# DBL_TLC5940_driver_for_High_load.net
KiCad netlist of a schematic drawn in Altium Designer
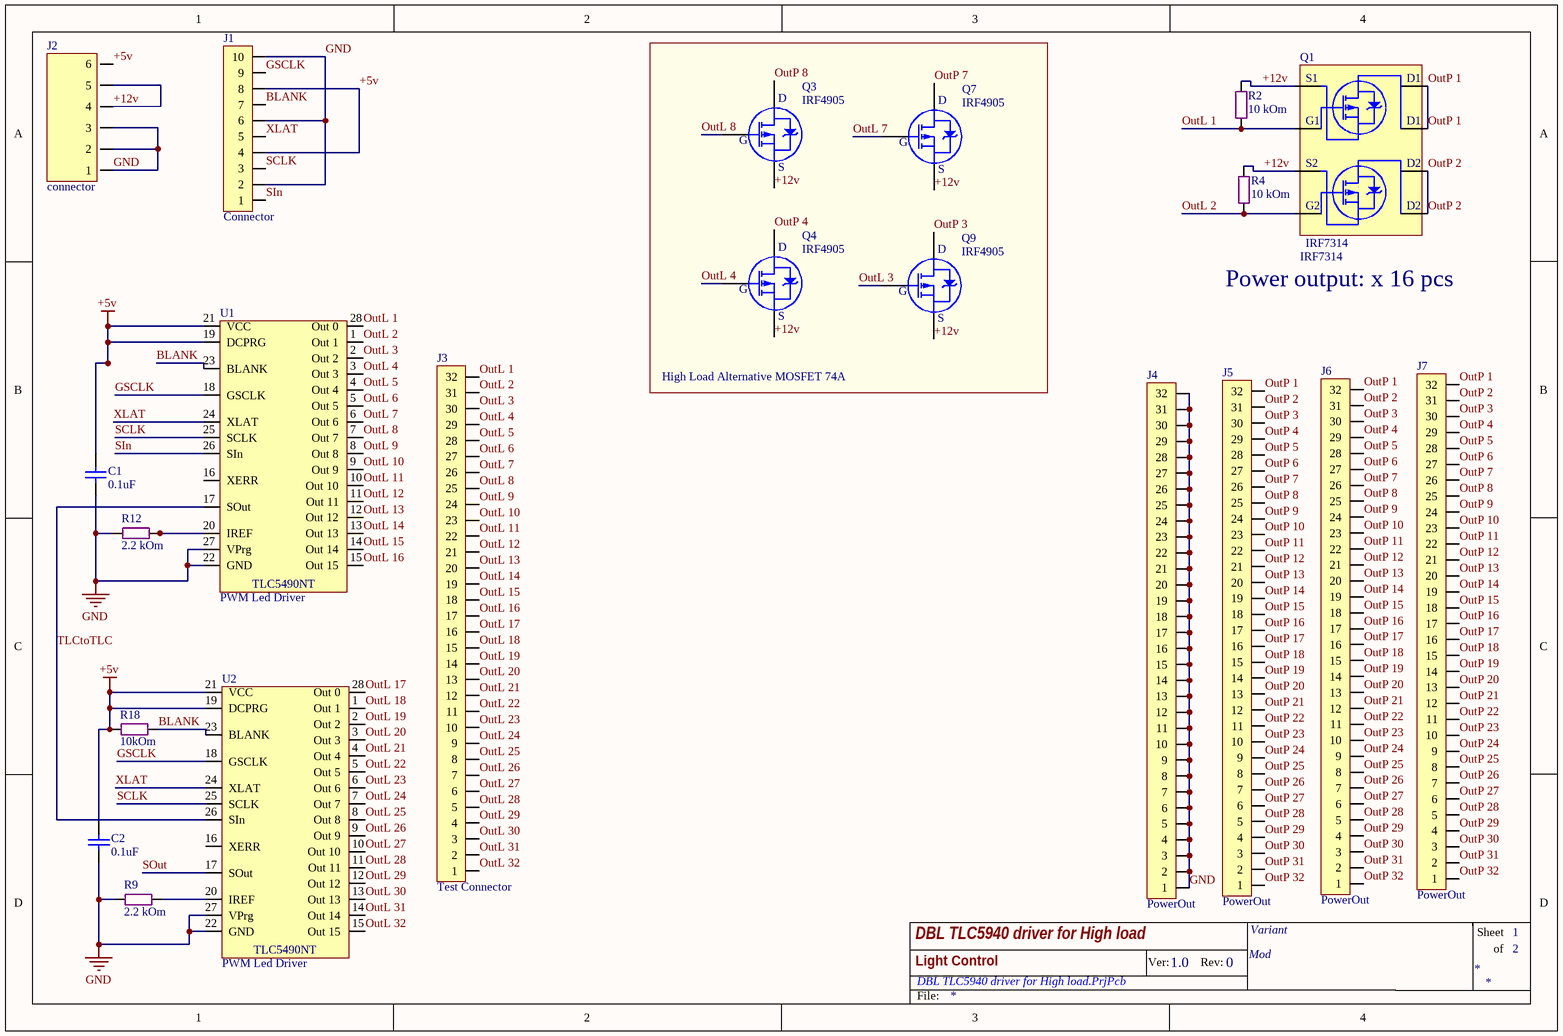
[diagram p0: DBL TLC5940 driver for High load.SchDoc]

(export (version "E")
  (design (tool "Eeschema 10.0.6"))
  (components
    (comp (ref "C1")
      (value "0.1uF")
      (footprint "Capacitor:SMD 0805 (2012)")
      (description "Capacitor")
      (libsource (lib "Capacitor") (part "Cap SMD 0402-1812"))
    )
    (comp (ref "C2")
      (value "0.1uF")
      (footprint "Capacitor:SMD 0805 (2012)")
      (description "Capacitor")
      (libsource (lib "Capacitor") (part "Cap SMD 0402-1812"))
    )
    (comp (ref "J1")
      (value "Connector")
      (footprint "Connector:LINE 2.54 x 10D (2 x 5) - BH")
      (description "Vert, Dbl line, Male")
      (libsource (lib "Connector") (part "PLD-10 (2 x 5)"))
    )
    (comp (ref "J2")
      (value "connector")
      (footprint "Connector:Molex Mini-Fit Jr - 6Pin R")
      (description "Right, Dbl line, Female")
      (libsource (lib "Connector") (part "Molex Mini-Fit Jr - 6 pin"))
    )
    (comp (ref "J3")
      (value "Test Connector")
      (footprint "Connector:LINE 2.54 x 32")
      (description "Vert, Sgl line, Male")
      (libsource (lib "Connector") (part "PLS-32"))
    )
    (comp (ref "J4")
      (value "PowerOut")
      (footprint "Connector:LINE 2.54 x 32")
      (description "Vert, Sgl line, Male")
      (libsource (lib "Connector") (part "PLS-32"))
    )
    (comp (ref "J5")
      (value "PowerOut")
      (footprint "Connector:LINE 2.54 x 32")
      (description "Vert, Sgl line, Male")
      (libsource (lib "Connector") (part "PLS-32"))
    )
    (comp (ref "J6")
      (value "PowerOut")
      (footprint "Connector:LINE 2.54 x 32")
      (description "Vert, Sgl line, Male")
      (libsource (lib "Connector") (part "PLS-32"))
    )
    (comp (ref "J7")
      (value "PowerOut")
      (footprint "Connector:LINE 2.54 x 32")
      (description "Vert, Sgl line, Male")
      (libsource (lib "Connector") (part "PLS-32"))
    )
    (comp (ref "Q1")
      (value "IRF7314")
      (footprint "GeneralCases:SO8")
      (description "Dual P-Ch  20V - 0.058Ω - 5.3A")
      (libsource (lib "Transistor") (part "IRF7314"))
    )
    (comp (ref "Q3")
      (value "IRF4905")
      (footprint "GeneralCases:TO220-2")
      (description "P-Channel 55V - 0.02Ω - 74A")
      (libsource (lib "Transistor") (part "IRF4905"))
    )
    (comp (ref "Q4")
      (value "IRF4905")
      (footprint "GeneralCases:TO220-2")
      (description "P-Channel 55V - 0.02Ω - 74A")
      (libsource (lib "Transistor") (part "IRF4905"))
    )
    (comp (ref "Q7")
      (value "IRF4905")
      (footprint "GeneralCases:TO220-2")
      (description "P-Channel 55V - 0.02Ω - 74A")
      (libsource (lib "Transistor") (part "IRF4905"))
    )
    (comp (ref "Q9")
      (value "IRF4905")
      (footprint "GeneralCases:TO220-2")
      (description "P-Channel 55V - 0.02Ω - 74A")
      (libsource (lib "Transistor") (part "IRF4905"))
    )
    (comp (ref "R2")
      (value "10 kOm")
      (footprint "PassiveComponents:SMD 0805 (2012)")
      (libsource (lib "PassiveComponents") (part "Res All Types"))
    )
    (comp (ref "R4")
      (value "10 kOm")
      (footprint "PassiveComponents:SMD 0805 (2012)")
      (libsource (lib "PassiveComponents") (part "Res All Types"))
    )
    (comp (ref "R9")
      (value "2.2 kOm")
      (footprint "PassiveComponents:SMD 0805 (2012)")
      (libsource (lib "PassiveComponents") (part "Res All Types"))
    )
    (comp (ref "R12")
      (value "2.2 kOm")
      (footprint "PassiveComponents:SMD 0805 (2012)")
      (libsource (lib "PassiveComponents") (part "Res All Types"))
    )
    (comp (ref "R18")
      (value "10kOm")
      (footprint "PassiveComponents:SMD 0805 (2012)")
      (libsource (lib "PassiveComponents") (part "Res All Types"))
    )
    (comp (ref "U1")
      (value "PWM Led Driver")
      (footprint "GeneralCases:DIP-28 (OVAL)")
      (description "16-Channel LED Driver With DOT Correction and Grayscale PWM Control")
      (libsource (lib "Chips") (part "TLC5940"))
    )
    (comp (ref "U2")
      (value "PWM Led Driver")
      (footprint "GeneralCases:DIP-28 (OVAL)")
      (description "16-Channel LED Driver With DOT Correction and Grayscale PWM Control")
      (libsource (lib "Chips") (part "TLC5940"))
    )
  )
  (nets
    (net (code "1") (name "+5v") (class "Default")
      (node (ref "C1") (pin "1") (pinfunction "1_1") (pintype "passive"))
      (node (ref "C2") (pin "1") (pinfunction "1_1") (pintype "passive"))
      (node (ref "J1") (pin "4") (pinfunction "4_4") (pintype "passive"))
      (node (ref "J1") (pin "8") (pinfunction "8_8") (pintype "passive"))
      (node (ref "J2") (pin "6") (pinfunction "6_6") (pintype "passive"))
      (node (ref "R18") (pin "1") (pinfunction "1_1") (pintype "passive"))
      (node (ref "U1") (pin "19") (pinfunction "DCPRG_19") (pintype "passive"))
      (node (ref "U1") (pin "21") (pinfunction "VCC_21") (pintype "passive"))
      (node (ref "U2") (pin "19") (pinfunction "DCPRG_19") (pintype "passive"))
      (node (ref "U2") (pin "21") (pinfunction "VCC_21") (pintype "passive"))
    )
    (net (code "2") (name "/+12v") (class "Default")
      (node (ref "J2") (pin "4") (pinfunction "4_4") (pintype "passive"))
      (node (ref "J2") (pin "5") (pinfunction "5_5") (pintype "passive"))
      (node (ref "Q1") (pin "1") (pinfunction "S_1") (pintype "passive"))
      (node (ref "Q1") (pin "3") (pinfunction "S_3") (pintype "passive"))
      (node (ref "Q3") (pin "3") (pinfunction "S_3") (pintype "passive"))
      (node (ref "Q4") (pin "3") (pinfunction "S_3") (pintype "passive"))
      (node (ref "Q7") (pin "3") (pinfunction "S_3") (pintype "passive"))
      (node (ref "Q9") (pin "3") (pinfunction "S_3") (pintype "passive"))
      (node (ref "R2") (pin "2") (pinfunction "2_2") (pintype "passive"))
      (node (ref "R4") (pin "2") (pinfunction "2_2") (pintype "passive"))
    )
    (net (code "3") (name "/BLANK") (class "Default")
      (node (ref "J1") (pin "7") (pinfunction "7_7") (pintype "passive"))
      (node (ref "R18") (pin "2") (pinfunction "2_2") (pintype "passive"))
      (node (ref "U1") (pin "23") (pinfunction "BLANK_23") (pintype "passive"))
      (node (ref "U2") (pin "23") (pinfunction "BLANK_23") (pintype "passive"))
    )
    (net (code "4") (name "/GSCLK") (class "Default")
      (node (ref "J1") (pin "9") (pinfunction "9_9") (pintype "passive"))
      (node (ref "U1") (pin "18") (pinfunction "GSCLK_18") (pintype "passive"))
      (node (ref "U2") (pin "18") (pinfunction "GSCLK_18") (pintype "passive"))
    )
    (net (code "5") (name "/OutL 1") (class "Default")
      (node (ref "J3") (pin "32") (pinfunction "32_32") (pintype "passive"))
      (node (ref "Q1") (pin "2") (pinfunction "G_2") (pintype "passive"))
      (node (ref "R2") (pin "1") (pinfunction "1_1") (pintype "passive"))
      (node (ref "U1") (pin "28") (pinfunction "Out_0_28") (pintype "passive"))
    )
    (net (code "6") (name "/OutL 2") (class "Default")
      (node (ref "J3") (pin "31") (pinfunction "31_31") (pintype "passive"))
      (node (ref "Q1") (pin "4") (pinfunction "G_4") (pintype "passive"))
      (node (ref "R4") (pin "1") (pinfunction "1_1") (pintype "passive"))
      (node (ref "U1") (pin "1") (pinfunction "Out_1_1") (pintype "passive"))
    )
    (net (code "7") (name "/OutL 3") (class "Default")
      (node (ref "J3") (pin "30") (pinfunction "30_30") (pintype "passive"))
      (node (ref "Q9") (pin "1") (pinfunction "G_1") (pintype "passive"))
      (node (ref "U1") (pin "2") (pinfunction "Out_2_2") (pintype "passive"))
    )
    (net (code "8") (name "/OutL 4") (class "Default")
      (node (ref "J3") (pin "29") (pinfunction "29_29") (pintype "passive"))
      (node (ref "Q4") (pin "1") (pinfunction "G_1") (pintype "passive"))
      (node (ref "U1") (pin "3") (pinfunction "Out_3_3") (pintype "passive"))
    )
    (net (code "9") (name "/OutL 5") (class "Default")
      (node (ref "J3") (pin "28") (pinfunction "28_28") (pintype "passive"))
      (node (ref "U1") (pin "4") (pinfunction "Out_4_4") (pintype "passive"))
    )
    (net (code "10") (name "/OutL 6") (class "Default")
      (node (ref "J3") (pin "27") (pinfunction "27_27") (pintype "passive"))
      (node (ref "U1") (pin "5") (pinfunction "Out_5_5") (pintype "passive"))
    )
    (net (code "11") (name "/OutL 7") (class "Default")
      (node (ref "J3") (pin "26") (pinfunction "26_26") (pintype "passive"))
      (node (ref "Q7") (pin "1") (pinfunction "G_1") (pintype "passive"))
      (node (ref "U1") (pin "6") (pinfunction "Out_6_6") (pintype "passive"))
    )
    (net (code "12") (name "/OutL 8") (class "Default")
      (node (ref "J3") (pin "25") (pinfunction "25_25") (pintype "passive"))
      (node (ref "Q3") (pin "1") (pinfunction "G_1") (pintype "passive"))
      (node (ref "U1") (pin "7") (pinfunction "Out_7_7") (pintype "passive"))
    )
    (net (code "13") (name "/OutL 9") (class "Default")
      (node (ref "J3") (pin "24") (pinfunction "24_24") (pintype "passive"))
      (node (ref "U1") (pin "8") (pinfunction "Out_8_8") (pintype "passive"))
    )
    (net (code "14") (name "/OutL 10") (class "Default")
      (node (ref "J3") (pin "23") (pinfunction "23_23") (pintype "passive"))
      (node (ref "U1") (pin "9") (pinfunction "Out_9_9") (pintype "passive"))
    )
    (net (code "15") (name "/OutL 11") (class "Default")
      (node (ref "J3") (pin "22") (pinfunction "22_22") (pintype "passive"))
      (node (ref "U1") (pin "10") (pinfunction "Out_10_10") (pintype "passive"))
    )
    (net (code "16") (name "/OutL 12") (class "Default")
      (node (ref "J3") (pin "21") (pinfunction "21_21") (pintype "passive"))
      (node (ref "U1") (pin "11") (pinfunction "Out_11_11") (pintype "passive"))
    )
    (net (code "17") (name "/OutL 13") (class "Default")
      (node (ref "J3") (pin "20") (pinfunction "20_20") (pintype "passive"))
      (node (ref "U1") (pin "12") (pinfunction "Out_12_12") (pintype "passive"))
    )
    (net (code "18") (name "/OutL 14") (class "Default")
      (node (ref "J3") (pin "19") (pinfunction "19_19") (pintype "passive"))
      (node (ref "U1") (pin "13") (pinfunction "Out_13_13") (pintype "passive"))
    )
    (net (code "19") (name "/OutL 15") (class "Default")
      (node (ref "J3") (pin "18") (pinfunction "18_18") (pintype "passive"))
      (node (ref "U1") (pin "14") (pinfunction "Out_14_14") (pintype "passive"))
    )
    (net (code "20") (name "/OutL 16") (class "Default")
      (node (ref "J3") (pin "17") (pinfunction "17_17") (pintype "passive"))
      (node (ref "U1") (pin "15") (pinfunction "Out_15_15") (pintype "passive"))
    )
    (net (code "21") (name "/OutL 17") (class "Default")
      (node (ref "J3") (pin "16") (pinfunction "16_16") (pintype "passive"))
      (node (ref "U2") (pin "28") (pinfunction "Out_0_28") (pintype "passive"))
    )
    (net (code "22") (name "/OutL 18") (class "Default")
      (node (ref "J3") (pin "15") (pinfunction "15_15") (pintype "passive"))
      (node (ref "U2") (pin "1") (pinfunction "Out_1_1") (pintype "passive"))
    )
    (net (code "23") (name "/OutL 19") (class "Default")
      (node (ref "J3") (pin "14") (pinfunction "14_14") (pintype "passive"))
      (node (ref "U2") (pin "2") (pinfunction "Out_2_2") (pintype "passive"))
    )
    (net (code "24") (name "/OutL 20") (class "Default")
      (node (ref "J3") (pin "13") (pinfunction "13_13") (pintype "passive"))
      (node (ref "U2") (pin "3") (pinfunction "Out_3_3") (pintype "passive"))
    )
    (net (code "25") (name "/OutL 21") (class "Default")
      (node (ref "J3") (pin "12") (pinfunction "12_12") (pintype "passive"))
      (node (ref "U2") (pin "4") (pinfunction "Out_4_4") (pintype "passive"))
    )
    (net (code "26") (name "/OutL 22") (class "Default")
      (node (ref "J3") (pin "11") (pinfunction "11_11") (pintype "passive"))
      (node (ref "U2") (pin "5") (pinfunction "Out_5_5") (pintype "passive"))
    )
    (net (code "27") (name "/OutL 23") (class "Default")
      (node (ref "J3") (pin "10") (pinfunction "10_10") (pintype "passive"))
      (node (ref "U2") (pin "6") (pinfunction "Out_6_6") (pintype "passive"))
    )
    (net (code "28") (name "/OutL 24") (class "Default")
      (node (ref "J3") (pin "9") (pinfunction "9_9") (pintype "passive"))
      (node (ref "U2") (pin "7") (pinfunction "Out_7_7") (pintype "passive"))
    )
    (net (code "29") (name "/OutL 25") (class "Default")
      (node (ref "J3") (pin "8") (pinfunction "8_8") (pintype "passive"))
      (node (ref "U2") (pin "8") (pinfunction "Out_8_8") (pintype "passive"))
    )
    (net (code "30") (name "/OutL 26") (class "Default")
      (node (ref "J3") (pin "7") (pinfunction "7_7") (pintype "passive"))
      (node (ref "U2") (pin "9") (pinfunction "Out_9_9") (pintype "passive"))
    )
    (net (code "31") (name "/OutL 27") (class "Default")
      (node (ref "J3") (pin "6") (pinfunction "6_6") (pintype "passive"))
      (node (ref "U2") (pin "10") (pinfunction "Out_10_10") (pintype "passive"))
    )
    (net (code "32") (name "/OutL 28") (class "Default")
      (node (ref "J3") (pin "5") (pinfunction "5_5") (pintype "passive"))
      (node (ref "U2") (pin "11") (pinfunction "Out_11_11") (pintype "passive"))
    )
    (net (code "33") (name "/OutL 29") (class "Default")
      (node (ref "J3") (pin "4") (pinfunction "4_4") (pintype "passive"))
      (node (ref "U2") (pin "12") (pinfunction "Out_12_12") (pintype "passive"))
    )
    (net (code "34") (name "/OutL 30") (class "Default")
      (node (ref "J3") (pin "3") (pinfunction "3_3") (pintype "passive"))
      (node (ref "U2") (pin "13") (pinfunction "Out_13_13") (pintype "passive"))
    )
    (net (code "35") (name "/OutL 31") (class "Default")
      (node (ref "J3") (pin "2") (pinfunction "2_2") (pintype "passive"))
      (node (ref "U2") (pin "14") (pinfunction "Out_14_14") (pintype "passive"))
    )
    (net (code "36") (name "/OutL 32") (class "Default")
      (node (ref "J3") (pin "1") (pinfunction "1_1") (pintype "passive"))
      (node (ref "U2") (pin "15") (pinfunction "Out_15_15") (pintype "passive"))
    )
    (net (code "37") (name "/OutP 1") (class "Default")
      (node (ref "J5") (pin "32") (pinfunction "32_32") (pintype "passive"))
      (node (ref "J6") (pin "32") (pinfunction "32_32") (pintype "passive"))
      (node (ref "J7") (pin "32") (pinfunction "32_32") (pintype "passive"))
      (node (ref "Q1") (pin "7") (pinfunction "D_7") (pintype "passive"))
      (node (ref "Q1") (pin "8") (pinfunction "D_8") (pintype "passive"))
    )
    (net (code "38") (name "/OutP 2") (class "Default")
      (node (ref "J5") (pin "31") (pinfunction "31_31") (pintype "passive"))
      (node (ref "J6") (pin "31") (pinfunction "31_31") (pintype "passive"))
      (node (ref "J7") (pin "31") (pinfunction "31_31") (pintype "passive"))
      (node (ref "Q1") (pin "5") (pinfunction "D_5") (pintype "passive"))
      (node (ref "Q1") (pin "6") (pinfunction "D_6") (pintype "passive"))
    )
    (net (code "39") (name "/OutP 3") (class "Default")
      (node (ref "J5") (pin "30") (pinfunction "30_30") (pintype "passive"))
      (node (ref "J6") (pin "30") (pinfunction "30_30") (pintype "passive"))
      (node (ref "J7") (pin "30") (pinfunction "30_30") (pintype "passive"))
      (node (ref "Q9") (pin "2") (pinfunction "D_2") (pintype "passive"))
    )
    (net (code "40") (name "/OutP 4") (class "Default")
      (node (ref "J5") (pin "29") (pinfunction "29_29") (pintype "passive"))
      (node (ref "J6") (pin "29") (pinfunction "29_29") (pintype "passive"))
      (node (ref "J7") (pin "29") (pinfunction "29_29") (pintype "passive"))
      (node (ref "Q4") (pin "2") (pinfunction "D_2") (pintype "passive"))
    )
    (net (code "41") (name "/OutP 5") (class "Default")
      (node (ref "J5") (pin "28") (pinfunction "28_28") (pintype "passive"))
      (node (ref "J6") (pin "28") (pinfunction "28_28") (pintype "passive"))
      (node (ref "J7") (pin "28") (pinfunction "28_28") (pintype "passive"))
    )
    (net (code "42") (name "/OutP 6") (class "Default")
      (node (ref "J5") (pin "27") (pinfunction "27_27") (pintype "passive"))
      (node (ref "J6") (pin "27") (pinfunction "27_27") (pintype "passive"))
      (node (ref "J7") (pin "27") (pinfunction "27_27") (pintype "passive"))
    )
    (net (code "43") (name "/OutP 7") (class "Default")
      (node (ref "J5") (pin "26") (pinfunction "26_26") (pintype "passive"))
      (node (ref "J6") (pin "26") (pinfunction "26_26") (pintype "passive"))
      (node (ref "J7") (pin "26") (pinfunction "26_26") (pintype "passive"))
      (node (ref "Q7") (pin "2") (pinfunction "D_2") (pintype "passive"))
    )
    (net (code "44") (name "/OutP 8") (class "Default")
      (node (ref "J5") (pin "25") (pinfunction "25_25") (pintype "passive"))
      (node (ref "J6") (pin "25") (pinfunction "25_25") (pintype "passive"))
      (node (ref "J7") (pin "25") (pinfunction "25_25") (pintype "passive"))
      (node (ref "Q3") (pin "2") (pinfunction "D_2") (pintype "passive"))
    )
    (net (code "45") (name "/OutP 9") (class "Default")
      (node (ref "J5") (pin "24") (pinfunction "24_24") (pintype "passive"))
      (node (ref "J6") (pin "24") (pinfunction "24_24") (pintype "passive"))
      (node (ref "J7") (pin "24") (pinfunction "24_24") (pintype "passive"))
    )
    (net (code "46") (name "/OutP 10") (class "Default")
      (node (ref "J5") (pin "23") (pinfunction "23_23") (pintype "passive"))
      (node (ref "J6") (pin "23") (pinfunction "23_23") (pintype "passive"))
      (node (ref "J7") (pin "23") (pinfunction "23_23") (pintype "passive"))
    )
    (net (code "47") (name "/OutP 11") (class "Default")
      (node (ref "J5") (pin "22") (pinfunction "22_22") (pintype "passive"))
      (node (ref "J6") (pin "22") (pinfunction "22_22") (pintype "passive"))
      (node (ref "J7") (pin "22") (pinfunction "22_22") (pintype "passive"))
    )
    (net (code "48") (name "/OutP 12") (class "Default")
      (node (ref "J5") (pin "21") (pinfunction "21_21") (pintype "passive"))
      (node (ref "J6") (pin "21") (pinfunction "21_21") (pintype "passive"))
      (node (ref "J7") (pin "21") (pinfunction "21_21") (pintype "passive"))
    )
    (net (code "49") (name "/OutP 13") (class "Default")
      (node (ref "J5") (pin "20") (pinfunction "20_20") (pintype "passive"))
      (node (ref "J6") (pin "20") (pinfunction "20_20") (pintype "passive"))
      (node (ref "J7") (pin "20") (pinfunction "20_20") (pintype "passive"))
    )
    (net (code "50") (name "/OutP 14") (class "Default")
      (node (ref "J5") (pin "19") (pinfunction "19_19") (pintype "passive"))
      (node (ref "J6") (pin "19") (pinfunction "19_19") (pintype "passive"))
      (node (ref "J7") (pin "19") (pinfunction "19_19") (pintype "passive"))
    )
    (net (code "51") (name "/OutP 15") (class "Default")
      (node (ref "J5") (pin "18") (pinfunction "18_18") (pintype "passive"))
      (node (ref "J6") (pin "18") (pinfunction "18_18") (pintype "passive"))
      (node (ref "J7") (pin "18") (pinfunction "18_18") (pintype "passive"))
    )
    (net (code "52") (name "/OutP 16") (class "Default")
      (node (ref "J5") (pin "17") (pinfunction "17_17") (pintype "passive"))
      (node (ref "J6") (pin "17") (pinfunction "17_17") (pintype "passive"))
      (node (ref "J7") (pin "17") (pinfunction "17_17") (pintype "passive"))
    )
    (net (code "53") (name "/OutP 17") (class "Default")
      (node (ref "J5") (pin "16") (pinfunction "16_16") (pintype "passive"))
      (node (ref "J6") (pin "16") (pinfunction "16_16") (pintype "passive"))
      (node (ref "J7") (pin "16") (pinfunction "16_16") (pintype "passive"))
    )
    (net (code "54") (name "/OutP 18") (class "Default")
      (node (ref "J5") (pin "15") (pinfunction "15_15") (pintype "passive"))
      (node (ref "J6") (pin "15") (pinfunction "15_15") (pintype "passive"))
      (node (ref "J7") (pin "15") (pinfunction "15_15") (pintype "passive"))
    )
    (net (code "55") (name "/OutP 19") (class "Default")
      (node (ref "J5") (pin "14") (pinfunction "14_14") (pintype "passive"))
      (node (ref "J6") (pin "14") (pinfunction "14_14") (pintype "passive"))
      (node (ref "J7") (pin "14") (pinfunction "14_14") (pintype "passive"))
    )
    (net (code "56") (name "/OutP 20") (class "Default")
      (node (ref "J5") (pin "13") (pinfunction "13_13") (pintype "passive"))
      (node (ref "J6") (pin "13") (pinfunction "13_13") (pintype "passive"))
      (node (ref "J7") (pin "13") (pinfunction "13_13") (pintype "passive"))
    )
    (net (code "57") (name "/OutP 21") (class "Default")
      (node (ref "J5") (pin "12") (pinfunction "12_12") (pintype "passive"))
      (node (ref "J6") (pin "12") (pinfunction "12_12") (pintype "passive"))
      (node (ref "J7") (pin "12") (pinfunction "12_12") (pintype "passive"))
    )
    (net (code "58") (name "/OutP 22") (class "Default")
      (node (ref "J5") (pin "11") (pinfunction "11_11") (pintype "passive"))
      (node (ref "J6") (pin "11") (pinfunction "11_11") (pintype "passive"))
      (node (ref "J7") (pin "11") (pinfunction "11_11") (pintype "passive"))
    )
    (net (code "59") (name "/OutP 23") (class "Default")
      (node (ref "J5") (pin "10") (pinfunction "10_10") (pintype "passive"))
      (node (ref "J6") (pin "10") (pinfunction "10_10") (pintype "passive"))
      (node (ref "J7") (pin "10") (pinfunction "10_10") (pintype "passive"))
    )
    (net (code "60") (name "/OutP 24") (class "Default")
      (node (ref "J5") (pin "9") (pinfunction "9_9") (pintype "passive"))
      (node (ref "J6") (pin "9") (pinfunction "9_9") (pintype "passive"))
      (node (ref "J7") (pin "9") (pinfunction "9_9") (pintype "passive"))
    )
    (net (code "61") (name "/OutP 25") (class "Default")
      (node (ref "J5") (pin "8") (pinfunction "8_8") (pintype "passive"))
      (node (ref "J6") (pin "8") (pinfunction "8_8") (pintype "passive"))
      (node (ref "J7") (pin "8") (pinfunction "8_8") (pintype "passive"))
    )
    (net (code "62") (name "/OutP 26") (class "Default")
      (node (ref "J5") (pin "7") (pinfunction "7_7") (pintype "passive"))
      (node (ref "J6") (pin "7") (pinfunction "7_7") (pintype "passive"))
      (node (ref "J7") (pin "7") (pinfunction "7_7") (pintype "passive"))
    )
    (net (code "63") (name "/OutP 27") (class "Default")
      (node (ref "J5") (pin "6") (pinfunction "6_6") (pintype "passive"))
      (node (ref "J6") (pin "6") (pinfunction "6_6") (pintype "passive"))
      (node (ref "J7") (pin "6") (pinfunction "6_6") (pintype "passive"))
    )
    (net (code "64") (name "/OutP 28") (class "Default")
      (node (ref "J5") (pin "5") (pinfunction "5_5") (pintype "passive"))
      (node (ref "J6") (pin "5") (pinfunction "5_5") (pintype "passive"))
      (node (ref "J7") (pin "5") (pinfunction "5_5") (pintype "passive"))
    )
    (net (code "65") (name "/OutP 29") (class "Default")
      (node (ref "J5") (pin "4") (pinfunction "4_4") (pintype "passive"))
      (node (ref "J6") (pin "4") (pinfunction "4_4") (pintype "passive"))
      (node (ref "J7") (pin "4") (pinfunction "4_4") (pintype "passive"))
    )
    (net (code "66") (name "/OutP 30") (class "Default")
      (node (ref "J5") (pin "3") (pinfunction "3_3") (pintype "passive"))
      (node (ref "J6") (pin "3") (pinfunction "3_3") (pintype "passive"))
      (node (ref "J7") (pin "3") (pinfunction "3_3") (pintype "passive"))
    )
    (net (code "67") (name "/OutP 31") (class "Default")
      (node (ref "J5") (pin "2") (pinfunction "2_2") (pintype "passive"))
      (node (ref "J6") (pin "2") (pinfunction "2_2") (pintype "passive"))
      (node (ref "J7") (pin "2") (pinfunction "2_2") (pintype "passive"))
    )
    (net (code "68") (name "/OutP 32") (class "Default")
      (node (ref "J5") (pin "1") (pinfunction "1_1") (pintype "passive"))
      (node (ref "J6") (pin "1") (pinfunction "1_1") (pintype "passive"))
      (node (ref "J7") (pin "1") (pinfunction "1_1") (pintype "passive"))
    )
    (net (code "69") (name "/SCLK") (class "Default")
      (node (ref "J1") (pin "3") (pinfunction "3_3") (pintype "passive"))
      (node (ref "U1") (pin "25") (pinfunction "SCLK_25") (pintype "passive"))
      (node (ref "U2") (pin "25") (pinfunction "SCLK_25") (pintype "passive"))
    )
    (net (code "70") (name "/SIn") (class "Default")
      (node (ref "J1") (pin "1") (pinfunction "1_1") (pintype "passive"))
      (node (ref "U1") (pin "26") (pinfunction "SIn_26") (pintype "passive"))
    )
    (net (code "71") (name "/SOut") (class "Default")
      (node (ref "U2") (pin "17") (pinfunction "SOut_17") (pintype "passive"))
    )
    (net (code "72") (name "/TLCtoTLC") (class "Default")
      (node (ref "U1") (pin "17") (pinfunction "SOut_17") (pintype "passive"))
      (node (ref "U2") (pin "26") (pinfunction "SIn_26") (pintype "passive"))
    )
    (net (code "73") (name "/XLAT") (class "Default")
      (node (ref "J1") (pin "5") (pinfunction "5_5") (pintype "passive"))
      (node (ref "U1") (pin "24") (pinfunction "XLAT_24") (pintype "passive"))
      (node (ref "U2") (pin "24") (pinfunction "XLAT_24") (pintype "passive"))
    )
    (net (code "74") (name "GND") (class "Default")
      (node (ref "C1") (pin "2") (pinfunction "2_2") (pintype "passive"))
      (node (ref "C2") (pin "2") (pinfunction "2_2") (pintype "passive"))
      (node (ref "J1") (pin "10") (pinfunction "10_10") (pintype "passive"))
      (node (ref "J1") (pin "2") (pinfunction "2_2") (pintype "passive"))
      (node (ref "J1") (pin "6") (pinfunction "6_6") (pintype "passive"))
      (node (ref "J2") (pin "1") (pinfunction "1_1") (pintype "passive"))
      (node (ref "J2") (pin "2") (pinfunction "2_2") (pintype "passive"))
      (node (ref "J2") (pin "3") (pinfunction "3_3") (pintype "passive"))
      (node (ref "J4") (pin "1") (pinfunction "1_1") (pintype "passive"))
      (node (ref "J4") (pin "10") (pinfunction "10_10") (pintype "passive"))
      (node (ref "J4") (pin "11") (pinfunction "11_11") (pintype "passive"))
      (node (ref "J4") (pin "12") (pinfunction "12_12") (pintype "passive"))
      (node (ref "J4") (pin "13") (pinfunction "13_13") (pintype "passive"))
      (node (ref "J4") (pin "14") (pinfunction "14_14") (pintype "passive"))
      (node (ref "J4") (pin "15") (pinfunction "15_15") (pintype "passive"))
      (node (ref "J4") (pin "16") (pinfunction "16_16") (pintype "passive"))
      (node (ref "J4") (pin "17") (pinfunction "17_17") (pintype "passive"))
      (node (ref "J4") (pin "18") (pinfunction "18_18") (pintype "passive"))
      (node (ref "J4") (pin "19") (pinfunction "19_19") (pintype "passive"))
      (node (ref "J4") (pin "2") (pinfunction "2_2") (pintype "passive"))
      (node (ref "J4") (pin "20") (pinfunction "20_20") (pintype "passive"))
      (node (ref "J4") (pin "21") (pinfunction "21_21") (pintype "passive"))
      (node (ref "J4") (pin "22") (pinfunction "22_22") (pintype "passive"))
      (node (ref "J4") (pin "23") (pinfunction "23_23") (pintype "passive"))
      (node (ref "J4") (pin "24") (pinfunction "24_24") (pintype "passive"))
      (node (ref "J4") (pin "25") (pinfunction "25_25") (pintype "passive"))
      (node (ref "J4") (pin "26") (pinfunction "26_26") (pintype "passive"))
      (node (ref "J4") (pin "27") (pinfunction "27_27") (pintype "passive"))
      (node (ref "J4") (pin "28") (pinfunction "28_28") (pintype "passive"))
      (node (ref "J4") (pin "29") (pinfunction "29_29") (pintype "passive"))
      (node (ref "J4") (pin "3") (pinfunction "3_3") (pintype "passive"))
      (node (ref "J4") (pin "30") (pinfunction "30_30") (pintype "passive"))
      (node (ref "J4") (pin "31") (pinfunction "31_31") (pintype "passive"))
      (node (ref "J4") (pin "32") (pinfunction "32_32") (pintype "passive"))
      (node (ref "J4") (pin "4") (pinfunction "4_4") (pintype "passive"))
      (node (ref "J4") (pin "5") (pinfunction "5_5") (pintype "passive"))
      (node (ref "J4") (pin "6") (pinfunction "6_6") (pintype "passive"))
      (node (ref "J4") (pin "7") (pinfunction "7_7") (pintype "passive"))
      (node (ref "J4") (pin "8") (pinfunction "8_8") (pintype "passive"))
      (node (ref "J4") (pin "9") (pinfunction "9_9") (pintype "passive"))
      (node (ref "R12") (pin "2") (pinfunction "2_2") (pintype "passive"))
      (node (ref "R9") (pin "2") (pinfunction "2_2") (pintype "passive"))
      (node (ref "U1") (pin "22") (pinfunction "GND_22") (pintype "passive"))
      (node (ref "U1") (pin "27") (pinfunction "VPrg_27") (pintype "passive"))
      (node (ref "U2") (pin "22") (pinfunction "GND_22") (pintype "passive"))
      (node (ref "U2") (pin "27") (pinfunction "VPrg_27") (pintype "passive"))
    )
    (net (code "75") (name "Net-(U1-IREF)") (class "Default")
      (node (ref "R12") (pin "1") (pinfunction "1_1") (pintype "passive"))
      (node (ref "U1") (pin "20") (pinfunction "IREF_20") (pintype "passive"))
    )
    (net (code "76") (name "Net-(U2-IREF)") (class "Default")
      (node (ref "R9") (pin "1") (pinfunction "1_1") (pintype "passive"))
      (node (ref "U2") (pin "20") (pinfunction "IREF_20") (pintype "passive"))
    )
    (net (code "77") (name "unconnected-(U1-XERR-Pad16)") (class "Default")
      (node (ref "U1") (pin "16") (pinfunction "XERR_16") (pintype "passive"))
    )
    (net (code "78") (name "unconnected-(U2-XERR-Pad16)") (class "Default")
      (node (ref "U2") (pin "16") (pinfunction "XERR_16") (pintype "passive"))
    )
  )
)
